# Boost-Shield-V2.net
KiCad netlist of a schematic drawn in Altium Designer
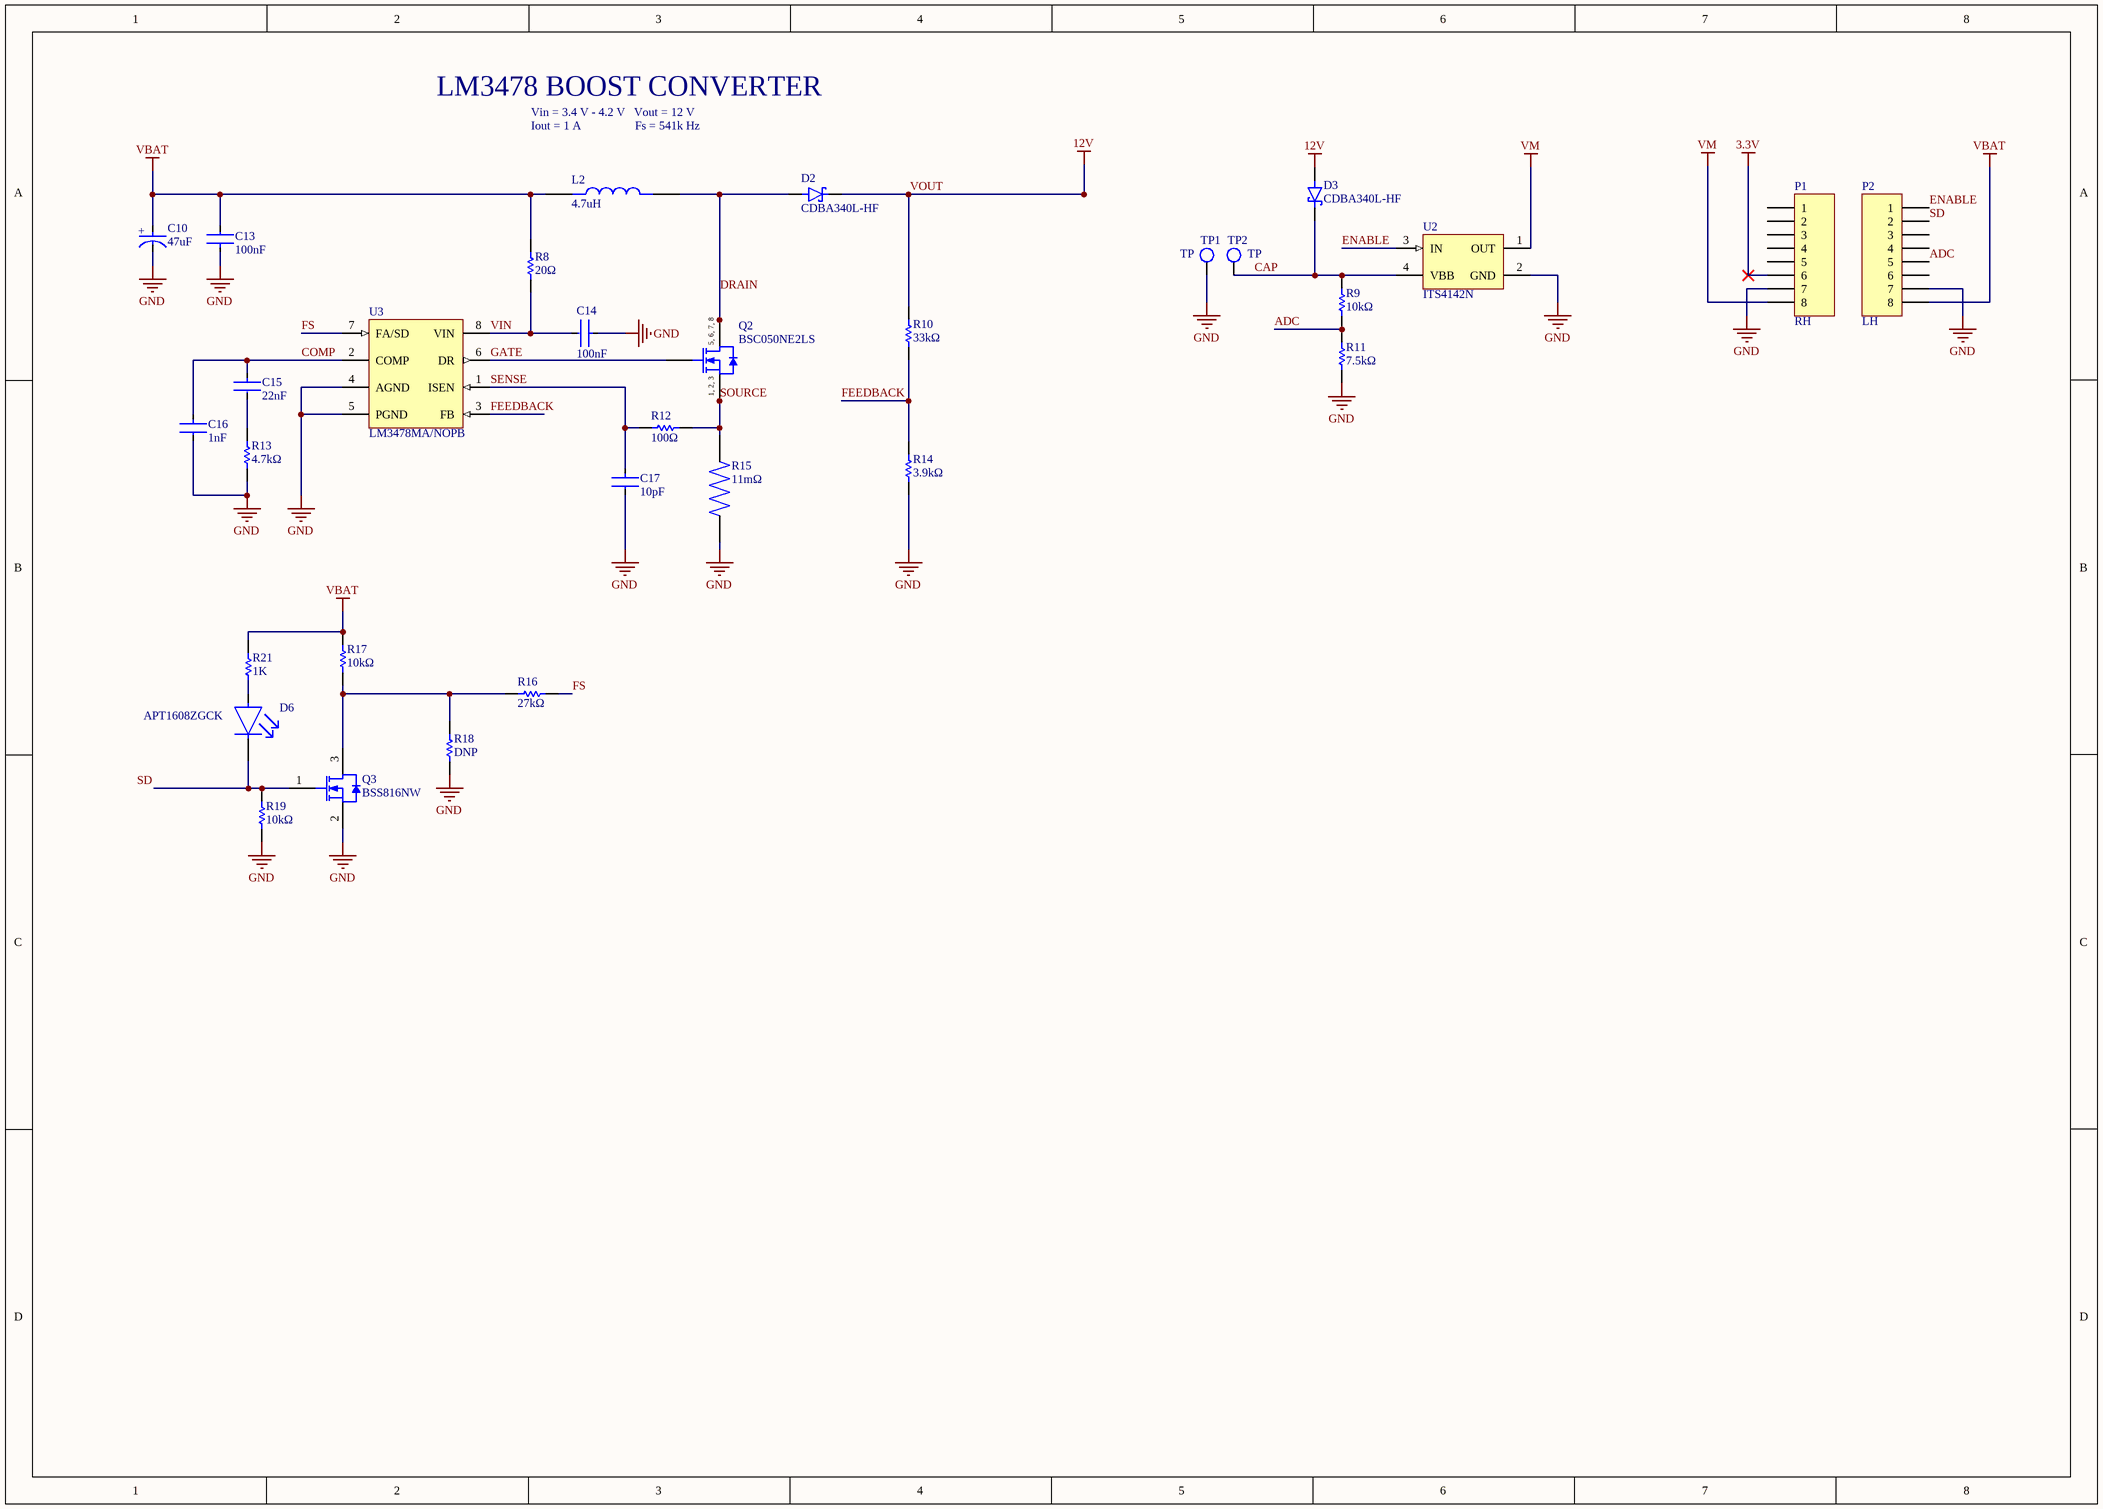
[diagram p0: Boost-Shield-V2.SchDoc]

(export (version "E")
  (design (tool "Eeschema 10.0.6"))
  (components
    (comp (ref "C10")
      (value "47uF")
      (footprint "FP-F38M-MFG")
      (description "CAP TANT POLY 47UF 6.3V SMD \r\nF380J476MMAAXEH3")
      (fields
        (field (name "OCTOPART") "https://octopart.com/f380j476mmaaxeh3-avx-67040374")
        (field (name "MANUFACTURER") "AVX")
      )
      (libsource (lib "Altium Content Vault") (part "cf48714ba7e38822c1575c7ec0b6d1f"))
    )
    (comp (ref "C13")
      (value "100nF")
      (footprint "FP-CL10-IPC_C")
      (description "Cap Ceramic 100nF 50V X7R ±20% Pad SMD 0603 +125°C T/R\r\nCL10B104MB8NNNC")
      (fields (field (name "TOLERANCE") "20%"))
      (libsource (lib "Altium Content Vault") (part "b4654b650e69147ec39a6b967a45e02"))
    )
    (comp (ref "C14")
      (value "100nF")
      (footprint "FP-CL10-IPC_C")
      (description "Cap Ceramic 100nF 50V X7R ±20% Pad SMD 0603 +125°C T/R\r\nCL10B104MB8NNNC")
      (fields (field (name "TOLERANCE") "20%"))
      (libsource (lib "Altium Content Vault") (part "b4654b650e69147ec39a6b967a45e02"))
    )
    (comp (ref "C15")
      (value "22nF")
      (footprint "FP-CC0603-DA-MFG")
      (description "0603 22 nF 50 V ±10 % Tolerance X7R SMT Multilayer Ceramic Capacitor\r\nCC0603KRX7R9BB223")
      (fields
        (field (name "MANUFACTURER") "YAGEO")
        (field (name "MANUFACTURER PART NUMBER") "CC0603KRX7R9BB223")
      )
      (libsource (lib "Altium Content Vault") (part "11868f565c42a9108669ba33697ecf6"))
    )
    (comp (ref "C16")
      (value "1nF")
      (footprint "FP-0603-L_1_6_0_15-W_0_81-IPC_C")
      (description "CAP CER 10000PF 50V X7R 0603\r\n06035C103KAT4A")
      (fields (field (name "TOLERANCE") "10%") (field (name "VOLTAGE") "50V"))
      (libsource (lib "Altium Content Vault") (part "02cd4be3c70576c341d710602a673aa"))
    )
    (comp (ref "C17")
      (value "10pF")
      (footprint "FP-C0603C-CF-MFG")
      (description "CAP CER 10PF 100V 5% NP0 0603\r\nC0603C100J1GACTU")
      (fields
        (field (name "MANUFACTURER PART NUMBER") "C0603C100J1GACTU")
        (field (name "MANUFACTURER") "KEMET")
      )
      (libsource (lib "Altium Content Vault") (part "b4654b650e69147ec39a6b967a45e02"))
    )
    (comp (ref "D2")
      (value "CDBA340L-HF")
      (footprint "DIOM5225X250N")
      (description "DIODE SCHOTTKY 40V 3A DO214AC")
      (fields (field (name "MANUFACTURER") "Comchip"))
      (libsource (lib "Boost-Shield") (part "CDBA340L-HF"))
    )
    (comp (ref "D3")
      (value "CDBA340L-HF")
      (footprint "DIOM5225X250N")
      (description "DIODE SCHOTTKY 40V 3A DO214AC")
      (fields (field (name "MANUFACTURER") "Comchip"))
      (libsource (lib "Boost-Shield") (part "CDBA340L-HF"))
    )
    (comp (ref "D6")
      (value "APT1608ZGCK")
      (footprint "FP-APT1608ZGCK-MFG")
      (description "LED GREEN CLEAR CHIP SMD")
      (libsource (lib "Altium Content Vault") (part "8706943c75ba83719d021d2fdc84c58"))
    )
    (comp (ref "L2")
      (value "4.7uH")
      (footprint "IND_ETQP4M4R7KFN")
      (description "Fixed Ind 4.7UH 7.3A 22.77MOHM")
      (fields
        (field (name "MANUFACTURER") "Panasonic")
        (field (name "MANUFACTURER PART NUMBER") "ETQ-P4M4R7KFN")
      )
      (libsource (lib "Boost-Shield") (part "ETQ-P4M4R7KFN"))
    )
    (comp (ref "P1")
      (value "RH")
      (footprint "HDR1X8")
      (description "Header, 8-Pin")
      (fields (field (name "PUBLISHER") "Altium Limited"))
      (libsource (lib "") (part "Header 8_1"))
    )
    (comp (ref "P2")
      (value "LH")
      (footprint "HDR1X8")
      (description "Header, 8-Pin")
      (fields (field (name "PUBLISHER") "Altium Limited"))
      (libsource (lib "Miscellaneous Connectors") (part "Header 8"))
    )
    (comp (ref "Q2")
      (value "BSC050NE2LS")
      (footprint "INF-PG-TDSON-8-1_V")
      (description "N-Channel OptiMOS Power-MOSFET, 25 V VDS, 58 A ID, -55 to 150 degC, PG-TDSON-8-1, Reel, Green")
      (fields (field (name "MANUFACTURER") "Infineon"))
      (libsource (lib "Altium Content Vault") (part "INF-NEMOS-SSSGDDDD-8"))
    )
    (comp (ref "Q3")
      (value "BSS816NW")
      (footprint "INF-PG-SOT-323_M")
      (fields (field (name "MANUFACTURER") "Infineon"))
      (libsource (lib "Altium Content Vault") (part "INF-NEMOS-GSD-3"))
    )
    (comp (ref "R8")
      (value "20Ω")
      (footprint "RESC1608X55X30ML15T15")
      (description "ERJ-3GEYJ200V")
      (fields (field (name "MANUFACTURER") "Panasonic"))
      (libsource (lib "Altium Content Vault") (part "RES"))
    )
    (comp (ref "R9")
      (value "10kΩ")
      (footprint "RESC1609X55X30LL15T15")
      (fields (field (name "TOLERANCE") "1%") (field (name "MANUFACTURER") "Panasonic"))
      (libsource (lib "Altium Content Vault") (part "RES-2"))
    )
    (comp (ref "R10")
      (value "33kΩ")
      (footprint "RESC1609X50X30LL10T20")
      (description "CRCW060333K0JNEA")
      (fields (field (name "MANUFACTURER") "Vishay Dale"))
      (libsource (lib "Altium Content Vault") (part "RES"))
    )
    (comp (ref "R11")
      (value "7.5kΩ")
      (footprint "RESC1609X50X30LL10T20")
      (description "CRCW06037K50FKEA")
      (fields (field (name "MANUFACTURER") "Vishay Dale"))
      (libsource (lib "Altium Content Vault") (part "RES"))
    )
    (comp (ref "R12")
      (value "100Ω")
      (footprint "RESC1609X50X30ML8T20")
      (fields (field (name "MANUFACTURER") "Vishay Semiconductor"))
      (libsource (lib "Altium Content Vault") (part "RES-2"))
    )
    (comp (ref "R13")
      (value "4.7kΩ")
      (footprint "RESC1608X55X30NL15T15")
      (fields (field (name "TOLERANCE") "5%"))
      (libsource (lib "Altium Content Vault") (part "RES-2"))
    )
    (comp (ref "R14")
      (value "3.9kΩ")
      (footprint "RESC1608X55X30LL15T15")
      (description "ERJ-3GEYJ392V")
      (fields (field (name "MANUFACTURER") "Panasonic"))
      (libsource (lib "Altium Content Vault") (part "RES"))
    )
    (comp (ref "R15")
      (value "11mΩ")
      (footprint "RESC3115X65N")
      (description "11 mOhms ±1% 0.5W, 1/2W Chip Resistor 1206 (3216 Metric) Current Sense Thick Film")
      (libsource (lib "Boost-Shield") (part "RLP73V2BR011FTDF"))
    )
    (comp (ref "R16")
      (value "27kΩ")
      (footprint "RESC1608X55X30ML15T15")
      (description "ERJ3EKF2702V")
      (fields (field (name "MANUFACTURER") "Panasonic"))
      (libsource (lib "Altium Content Vault") (part "RES"))
    )
    (comp (ref "R17")
      (value "10kΩ")
      (footprint "RESC1609X55X30LL15T15")
      (fields (field (name "TOLERANCE") "1%") (field (name "MANUFACTURER") "Panasonic"))
      (libsource (lib "Altium Content Vault") (part "RES-2"))
    )
    (comp (ref "R18")
      (value "DNP")
      (footprint "RESC1608X55X25ML10T15")
      (fields (field (name "TOLERANCE") "5%") (field (name "MANUFACTURER") "Yageo"))
      (libsource (lib "Altium Content Vault") (part "RES-2"))
    )
    (comp (ref "R19")
      (value "10kΩ")
      (footprint "RESC1609X55X30LL15T15")
      (fields (field (name "TOLERANCE") "1%") (field (name "MANUFACTURER") "Panasonic"))
      (libsource (lib "Altium Content Vault") (part "RES-2"))
    )
    (comp (ref "R21")
      (value "1K")
      (footprint "RESC1608X55X25NL10T15")
      (description "Chip Resistor, 1 KOhm, +/-1%, 0.1 W, -55 to 155 degC, 0603 (1608 Metric), RoHS, Tape and Reel")
      (fields (field (name "MANUFACTURER") "Yageo"))
      (libsource (lib "Altium Content Vault") (part "RES-2"))
    )
    (comp (ref "TP1") (value "TP") (footprint "TP") (libsource (lib "Boost-Shield") (part "TP")))
    (comp (ref "TP2") (value "TP") (footprint "TP") (libsource (lib "Boost-Shield") (part "TP")))
    (comp (ref "U2")
      (value "ITS4142N")
      (footprint "INF-SOT223_M")
      (fields (field (name "MANUFACTURER") "Infineon"))
      (libsource (lib "Altium Content Vault") (part "INF-ITS4142N-SOT223-4"))
    )
    (comp (ref "U3")
      (value "LM3478MA/NOPB")
      (footprint "D0008A_L")
      (fields (field (name "MANUFACTURER") "Texas Instruments"))
      (libsource (lib "Altium Content Vault") (part "PM-SWREG-LM3478-8"))
    )
  )
  (nets
    (net (code "1") (name "/ADC") (class "Default")
      (node (ref "P2") (pin "5") (pinfunction "5_5") (pintype "passive"))
      (node (ref "R11") (pin "2") (pinfunction "2_2") (pintype "passive"))
      (node (ref "R9") (pin "1") (pinfunction "1_1") (pintype "passive"))
    )
    (net (code "2") (name "/CAP") (class "Default")
      (node (ref "D3") (pin "C") (pinfunction "K_C") (pintype "passive"))
      (node (ref "R9") (pin "2") (pinfunction "2_2") (pintype "passive"))
      (node (ref "TP2") (pin "1") (pinfunction "1_1") (pintype "passive"))
      (node (ref "U2") (pin "4") (pinfunction "VBB_4") (pintype "power_in"))
    )
    (net (code "3") (name "/COMP") (class "Default")
      (node (ref "C15") (pin "1") (pinfunction "1_1") (pintype "passive"))
      (node (ref "C16") (pin "1") (pinfunction "1_1") (pintype "passive"))
      (node (ref "U3") (pin "2") (pinfunction "COMP_2") (pintype "passive"))
    )
    (net (code "4") (name "/DRAIN") (class "Default")
      (node (ref "D2") (pin "A") (pinfunction "A_A") (pintype "passive"))
      (node (ref "L2") (pin "2") (pinfunction "2_2") (pintype "passive"))
      (node (ref "Q2") (pin "5") (pinfunction "DRAIN_5") (pintype "passive"))
      (node (ref "Q2") (pin "6") (pinfunction "DRAIN_6") (pintype "passive"))
      (node (ref "Q2") (pin "7") (pinfunction "DRAIN_7") (pintype "passive"))
      (node (ref "Q2") (pin "8") (pinfunction "DRAIN_8") (pintype "passive"))
    )
    (net (code "5") (name "/ENABLE") (class "Default")
      (node (ref "P2") (pin "1") (pinfunction "1_1") (pintype "passive"))
      (node (ref "U2") (pin "3") (pinfunction "IN_3") (pintype "input"))
    )
    (net (code "6") (name "/FEEDBACK") (class "Default")
      (node (ref "R10") (pin "1") (pinfunction "1_1") (pintype "passive"))
      (node (ref "R14") (pin "2") (pinfunction "2_2") (pintype "passive"))
      (node (ref "U3") (pin "3") (pinfunction "FB_3") (pintype "input"))
    )
    (net (code "7") (name "/FS") (class "Default")
      (node (ref "R16") (pin "2") (pinfunction "2_2") (pintype "passive"))
      (node (ref "U3") (pin "7") (pinfunction "FA/SD_7") (pintype "input"))
    )
    (net (code "8") (name "/GATE") (class "Default")
      (node (ref "Q2") (pin "4") (pinfunction "GATE_4") (pintype "passive"))
      (node (ref "U3") (pin "6") (pinfunction "DR_6") (pintype "output"))
    )
    (net (code "9") (name "/SD") (class "Default")
      (node (ref "D6") (pin "1") (pinfunction "C_1") (pintype "passive"))
      (node (ref "P2") (pin "2") (pinfunction "2_2") (pintype "passive"))
      (node (ref "Q3") (pin "1") (pinfunction "GATE_1") (pintype "passive"))
      (node (ref "R19") (pin "2") (pinfunction "2_2") (pintype "passive"))
    )
    (net (code "10") (name "/SENSE") (class "Default")
      (node (ref "C17") (pin "1") (pinfunction "1_1") (pintype "passive"))
      (node (ref "R12") (pin "1") (pinfunction "1_1") (pintype "passive"))
      (node (ref "U3") (pin "1") (pinfunction "ISEN_1") (pintype "input"))
    )
    (net (code "11") (name "/SOURCE") (class "Default")
      (node (ref "Q2") (pin "1") (pinfunction "SOURCE_1") (pintype "passive"))
      (node (ref "Q2") (pin "2") (pinfunction "SOURCE_2") (pintype "passive"))
      (node (ref "Q2") (pin "3") (pinfunction "SOURCE_3") (pintype "passive"))
      (node (ref "R12") (pin "2") (pinfunction "2_2") (pintype "passive"))
      (node (ref "R15") (pin "2") (pinfunction "2_2") (pintype "passive"))
    )
    (net (code "12") (name "/VIN") (class "Default")
      (node (ref "C14") (pin "2") (pinfunction "2_2") (pintype "passive"))
      (node (ref "R8") (pin "1") (pinfunction "1_1") (pintype "passive"))
      (node (ref "U3") (pin "8") (pinfunction "VIN_8") (pintype "power_in"))
    )
    (net (code "13") (name "3.3V") (class "Default")
      (node (ref "P1") (pin "6") (pinfunction "6_6") (pintype "passive"))
    )
    (net (code "14") (name "12V") (class "Default")
      (node (ref "D2") (pin "C") (pinfunction "K_C") (pintype "passive"))
      (node (ref "D3") (pin "A") (pinfunction "A_A") (pintype "passive"))
      (node (ref "R10") (pin "2") (pinfunction "2_2") (pintype "passive"))
    )
    (net (code "15") (name "GND") (class "Default")
      (node (ref "C10") (pin "1") (pinfunction "C_1") (pintype "passive"))
      (node (ref "C13") (pin "1") (pinfunction "1_1") (pintype "passive"))
      (node (ref "C14") (pin "1") (pinfunction "1_1") (pintype "passive"))
      (node (ref "C16") (pin "2") (pinfunction "2_2") (pintype "passive"))
      (node (ref "C17") (pin "2") (pinfunction "2_2") (pintype "passive"))
      (node (ref "P1") (pin "7") (pinfunction "7_7") (pintype "passive"))
      (node (ref "P2") (pin "7") (pinfunction "7_7") (pintype "passive"))
      (node (ref "Q3") (pin "2") (pinfunction "SOURCE_2") (pintype "passive"))
      (node (ref "R11") (pin "1") (pinfunction "1_1") (pintype "passive"))
      (node (ref "R13") (pin "1") (pinfunction "1_1") (pintype "passive"))
      (node (ref "R14") (pin "1") (pinfunction "1_1") (pintype "passive"))
      (node (ref "R15") (pin "1") (pinfunction "1_1") (pintype "passive"))
      (node (ref "R18") (pin "1") (pinfunction "1_1") (pintype "passive"))
      (node (ref "R19") (pin "1") (pinfunction "1_1") (pintype "passive"))
      (node (ref "TP1") (pin "1") (pinfunction "1_1") (pintype "passive"))
      (node (ref "U2") (pin "2") (pinfunction "GND_2") (pintype "power_in"))
      (node (ref "U3") (pin "4") (pinfunction "AGND_4") (pintype "power_in"))
      (node (ref "U3") (pin "5") (pinfunction "PGND_5") (pintype "power_in"))
    )
    (net (code "16") (name "Net-(C15-Pad2)") (class "Default")
      (node (ref "C15") (pin "2") (pinfunction "2_2") (pintype "passive"))
      (node (ref "R13") (pin "2") (pinfunction "2_2") (pintype "passive"))
    )
    (net (code "17") (name "Net-(D6-A)") (class "Default")
      (node (ref "D6") (pin "2") (pinfunction "A_2") (pintype "passive"))
      (node (ref "R21") (pin "1") (pinfunction "1_1") (pintype "passive"))
    )
    (net (code "18") (name "Net-(Q3-DRAIN)") (class "Default")
      (node (ref "Q3") (pin "3") (pinfunction "DRAIN_3") (pintype "passive"))
      (node (ref "R16") (pin "1") (pinfunction "1_1") (pintype "passive"))
      (node (ref "R17") (pin "1") (pinfunction "1_1") (pintype "passive"))
      (node (ref "R18") (pin "2") (pinfunction "2_2") (pintype "passive"))
    )
    (net (code "19") (name "VBAT") (class "Default")
      (node (ref "C10") (pin "2") (pinfunction "A_2") (pintype "passive"))
      (node (ref "C13") (pin "2") (pinfunction "2_2") (pintype "passive"))
      (node (ref "L2") (pin "1") (pinfunction "1_1") (pintype "passive"))
      (node (ref "P2") (pin "8") (pinfunction "8_8") (pintype "passive"))
      (node (ref "R17") (pin "2") (pinfunction "2_2") (pintype "passive"))
      (node (ref "R21") (pin "2") (pinfunction "2_2") (pintype "passive"))
      (node (ref "R8") (pin "2") (pinfunction "2_2") (pintype "passive"))
    )
    (net (code "20") (name "VM") (class "Default")
      (node (ref "P1") (pin "8") (pinfunction "8_8") (pintype "passive"))
      (node (ref "U2") (pin "1") (pinfunction "OUT_1") (pintype "power_in"))
    )
    (net (code "21") (name "unconnected-(P1-Pad1)") (class "Default")
      (node (ref "P1") (pin "1") (pinfunction "1_1") (pintype "passive"))
    )
    (net (code "22") (name "unconnected-(P1-Pad2)") (class "Default")
      (node (ref "P1") (pin "2") (pinfunction "2_2") (pintype "passive"))
    )
    (net (code "23") (name "unconnected-(P1-Pad3)") (class "Default")
      (node (ref "P1") (pin "3") (pinfunction "3_3") (pintype "passive"))
    )
    (net (code "24") (name "unconnected-(P1-Pad4)") (class "Default")
      (node (ref "P1") (pin "4") (pinfunction "4_4") (pintype "passive"))
    )
    (net (code "25") (name "unconnected-(P1-Pad5)") (class "Default")
      (node (ref "P1") (pin "5") (pinfunction "5_5") (pintype "passive"))
    )
    (net (code "26") (name "unconnected-(P2-Pad3)") (class "Default")
      (node (ref "P2") (pin "3") (pinfunction "3_3") (pintype "passive"))
    )
    (net (code "27") (name "unconnected-(P2-Pad4)") (class "Default")
      (node (ref "P2") (pin "4") (pinfunction "4_4") (pintype "passive"))
    )
    (net (code "28") (name "unconnected-(P2-Pad6)") (class "Default")
      (node (ref "P2") (pin "6") (pinfunction "6_6") (pintype "passive"))
    )
  )
)
